# I2C.net
KiCad netlist of a schematic drawn in Altium Designer
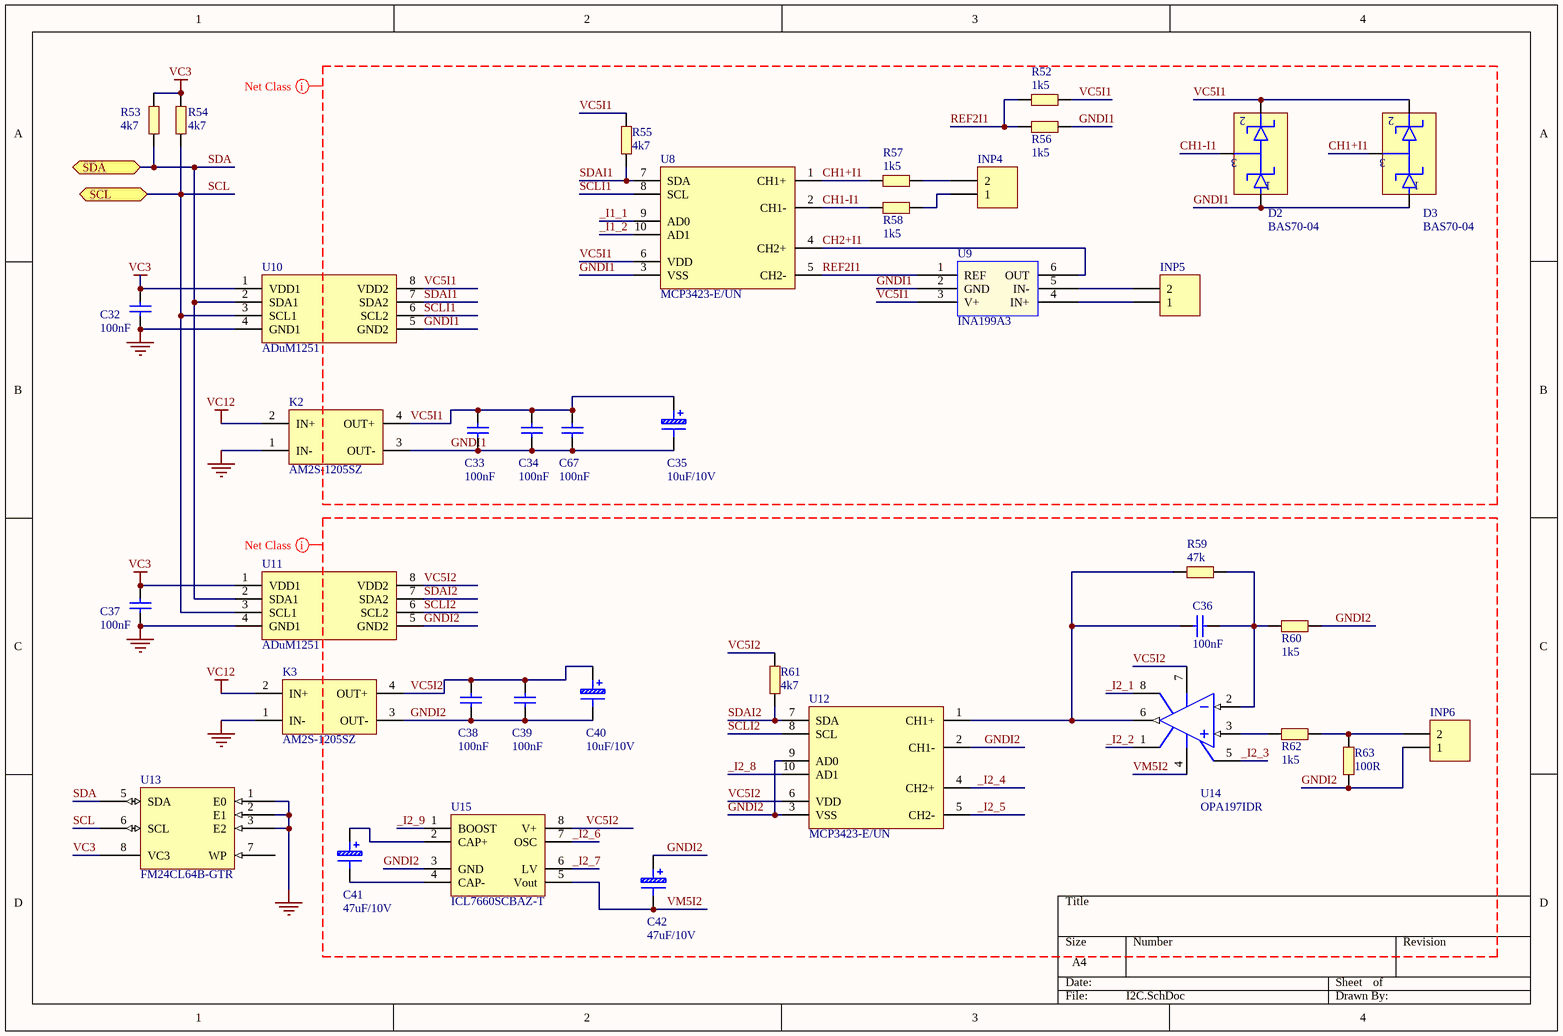
[diagram p0: I2C.SchDoc]

(export (version "E")
  (design (tool "Eeschema 10.0.6"))
  (components
    (comp (ref "C32")
      (value "100nF")
      (footprint "0603C")
      (description "Capacitor,100nF,16V,X7R,10%,0402,YAGEO")
      (libsource (lib "MCD_TOOLS") (part "Cap_100nF_X7R_10%_0402"))
    )
    (comp (ref "C33")
      (value "100nF")
      (footprint "0603C")
      (description "Capacitor,100nF,16V,X7R,10%,0402,YAGEO")
      (libsource (lib "MCD_TOOLS") (part "Cap_100nF_X7R_10%_0402"))
    )
    (comp (ref "C34")
      (value "100nF")
      (footprint "0603C")
      (description "Capacitor,100nF,16V,X7R,10%,0402,YAGEO")
      (libsource (lib "MCD_TOOLS") (part "Cap_100nF_X7R_10%_0402"))
    )
    (comp (ref "C35") (value "10uF/10V") (footprint "CAP_A") (libsource (lib "GkSchlib") (part "CapTantal")))
    (comp (ref "C36")
      (value "100nF")
      (footprint "0603C")
      (description "Capacitor,100nF,16V,X7R,10%,0402,YAGEO")
      (libsource (lib "MCD_TOOLS") (part "Cap_100nF_X7R_10%_0402"))
    )
    (comp (ref "C37")
      (value "100nF")
      (footprint "0603C")
      (description "Capacitor,100nF,16V,X7R,10%,0402,YAGEO")
      (libsource (lib "MCD_TOOLS") (part "Cap_100nF_X7R_10%_0402"))
    )
    (comp (ref "C38")
      (value "100nF")
      (footprint "0603C")
      (description "Capacitor,100nF,16V,X7R,10%,0402,YAGEO")
      (libsource (lib "MCD_TOOLS") (part "Cap_100nF_X7R_10%_0402"))
    )
    (comp (ref "C39")
      (value "100nF")
      (footprint "0603C")
      (description "Capacitor,100nF,16V,X7R,10%,0402,YAGEO")
      (libsource (lib "MCD_TOOLS") (part "Cap_100nF_X7R_10%_0402"))
    )
    (comp (ref "C40") (value "10uF/10V") (footprint "CAP_A") (libsource (lib "GkSchlib") (part "CapTantal")))
    (comp (ref "C41") (value "47uF/10V") (footprint "CAP_C") (libsource (lib "GkSchlib") (part "CapTantal")))
    (comp (ref "C42") (value "47uF/10V") (footprint "CAP_C") (libsource (lib "GkSchlib") (part "CapTantal")))
    (comp (ref "C67")
      (value "100nF")
      (footprint "0603C")
      (description "Capacitor,100nF,16V,X7R,10%,0402,YAGEO")
      (libsource (lib "MCD_TOOLS") (part "Cap_100nF_X7R_10%_0402"))
    )
    (comp (ref "D2") (value "BAS70-04") (footprint "SOT-23") (libsource (lib "*") (part "BAS70-04")))
    (comp (ref "D3") (value "BAS70-04") (footprint "SOT-23") (libsource (lib "*") (part "BAS70-04")))
    (comp (ref "INP4")
      (value "Header 2")
      (footprint "JST-XH-2Y-2.54")
      (description "Header, 2-Pin")
      (fields (field (name "PUBLISHER") "Altium Limited"))
      (libsource (lib "Miscellaneous Connectors") (part "Header 2"))
    )
    (comp (ref "INP5")
      (value "Header 2")
      (footprint "JST-XH-2Y-2.54")
      (description "Header, 2-Pin")
      (fields (field (name "PUBLISHER") "Altium Limited"))
      (libsource (lib "Miscellaneous Connectors") (part "Header 2"))
    )
    (comp (ref "INP6")
      (value "Header 2")
      (footprint "JST-XH-2Y-2.54")
      (description "Header, 2-Pin")
      (fields (field (name "PUBLISHER") "Altium Limited"))
      (libsource (lib "Miscellaneous Connectors") (part "Header 2"))
    )
    (comp (ref "K2")
      (value "AM2S-1205SZ")
      (footprint "DCDC_SIL4")
      (libsource (lib "GkSchlib") (part "DCDC_SIL"))
    )
    (comp (ref "K3")
      (value "AM2S-1205SZ")
      (footprint "DCDC_SIL4")
      (libsource (lib "GkSchlib") (part "DCDC_SIL"))
    )
    (comp (ref "R52") (value "1k5") (footprint "0603R") (libsource (lib "") (part "RES3_2")))
    (comp (ref "R53") (value "4k7") (footprint "0603R") (libsource (lib "*") (part "RES3")))
    (comp (ref "R54") (value "4k7") (footprint "0603R") (libsource (lib "*") (part "RES3")))
    (comp (ref "R55") (value "4k7") (footprint "0603R") (libsource (lib "") (part "RES3_1")))
    (comp (ref "R56") (value "1k5") (footprint "0603R") (libsource (lib "") (part "RES3_2")))
    (comp (ref "R57") (value "1k5") (footprint "0603R") (libsource (lib "") (part "RES3_2")))
    (comp (ref "R58") (value "1k5") (footprint "0603R") (libsource (lib "") (part "RES3_2")))
    (comp (ref "R59") (value "47k") (footprint "0603R") (libsource (lib "") (part "RES3_2")))
    (comp (ref "R60") (value "1k5") (footprint "0603R") (libsource (lib "") (part "RES3_2")))
    (comp (ref "R61") (value "4k7") (footprint "0603R") (libsource (lib "") (part "RES3_1")))
    (comp (ref "R62") (value "1k5") (footprint "0603R") (libsource (lib "") (part "RES3_2")))
    (comp (ref "R63") (value "100R") (footprint "0603R") (libsource (lib "") (part "RES3_1")))
    (comp (ref "U8")
      (value "MCP3423-E/UN")
      (footprint "MSOP10_1")
      (libsource (lib "GkSchlib") (part "MCP3423"))
    )
    (comp (ref "U9") (value "INA199A3") (footprint "SC70-6") (libsource (lib "GkSchlib") (part "INA199")))
    (comp (ref "U10")
      (value "ADuM1251")
      (footprint "SO8")
      (description "ADuM1251ARZ")
      (libsource (lib "GkSchlib") (part "ADuM1251"))
    )
    (comp (ref "U11")
      (value "ADuM1251")
      (footprint "SO8")
      (description "ADuM1251ARZ")
      (libsource (lib "GkSchlib") (part "ADuM1251"))
    )
    (comp (ref "U12")
      (value "MCP3423-E/UN")
      (footprint "MSOP10_1")
      (libsource (lib "GkSchlib") (part "MCP3423"))
    )
    (comp (ref "U13") (value "FM24CL64B-GTR") (footprint "SO8") (libsource (lib "*") (part "AT24C02")))
    (comp (ref "U14")
      (value "OPA197IDR")
      (footprint "SO8")
      (description "FET Operational Amplifier")
      (fields (field (name "PUBLISHER") "Altium Limited"))
      (libsource (lib "Miscellaneous Devices") (part "Op Amp"))
    )
    (comp (ref "U15")
      (value "ICL7660SCBAZ-T")
      (footprint "SO8")
      (libsource (lib "GkSchlib") (part "ICL7660"))
    )
  )
  (nets
    (net (code "1") (name "/CH1+I1") (class "Default")
      (node (ref "D3") (pin "3") (pintype "passive"))
      (node (ref "R57") (pin "1") (pintype "passive"))
      (node (ref "U8") (pin "1") (pinfunction "CH1+_1") (pintype "passive"))
    )
    (net (code "2") (name "/CH1-I1") (class "Default")
      (node (ref "D2") (pin "3") (pintype "passive"))
      (node (ref "R58") (pin "1") (pintype "passive"))
      (node (ref "U8") (pin "2") (pinfunction "CH1-_2") (pintype "passive"))
    )
    (net (code "3") (name "/CH2+I1") (class "Default")
      (node (ref "U8") (pin "4") (pinfunction "CH2+_4") (pintype "passive"))
      (node (ref "U9") (pin "6") (pinfunction "OUT_6") (pintype "passive"))
    )
    (net (code "4") (name "/GNDI1") (class "Default")
      (node (ref "C33") (pin "1") (pinfunction "1_1") (pintype "passive"))
      (node (ref "C34") (pin "1") (pinfunction "1_1") (pintype "passive"))
      (node (ref "C35") (pin "1") (pintype "passive"))
      (node (ref "C67") (pin "1") (pinfunction "1_1") (pintype "passive"))
      (node (ref "D2") (pin "1") (pintype "passive"))
      (node (ref "D3") (pin "1") (pintype "passive"))
      (node (ref "K2") (pin "3") (pinfunction "OUT-_3") (pintype "passive"))
      (node (ref "R56") (pin "2") (pintype "passive"))
      (node (ref "U10") (pin "5") (pinfunction "GND2_5") (pintype "passive"))
      (node (ref "U8") (pin "3") (pinfunction "VSS_3") (pintype "passive"))
      (node (ref "U9") (pin "2") (pinfunction "GND_2") (pintype "passive"))
    )
    (net (code "5") (name "/GNDI2") (class "Default")
      (node (ref "C38") (pin "1") (pinfunction "1_1") (pintype "passive"))
      (node (ref "C39") (pin "1") (pinfunction "1_1") (pintype "passive"))
      (node (ref "C40") (pin "1") (pintype "passive"))
      (node (ref "C42") (pin "2") (pintype "passive"))
      (node (ref "INP6") (pin "1") (pinfunction "1_1") (pintype "passive"))
      (node (ref "K3") (pin "3") (pinfunction "OUT-_3") (pintype "passive"))
      (node (ref "R60") (pin "2") (pintype "passive"))
      (node (ref "R63") (pin "1") (pintype "passive"))
      (node (ref "U11") (pin "5") (pinfunction "GND2_5") (pintype "passive"))
      (node (ref "U12") (pin "2") (pinfunction "CH1-_2") (pintype "passive"))
      (node (ref "U12") (pin "3") (pinfunction "VSS_3") (pintype "passive"))
      (node (ref "U12") (pin "9") (pinfunction "AD0_9") (pintype "passive"))
      (node (ref "U15") (pin "3") (pinfunction "GND_3") (pintype "passive"))
    )
    (net (code "6") (name "/REF2I1") (class "Default")
      (node (ref "R52") (pin "1") (pintype "passive"))
      (node (ref "R56") (pin "1") (pintype "passive"))
      (node (ref "U8") (pin "5") (pinfunction "CH2-_5") (pintype "passive"))
      (node (ref "U9") (pin "1") (pinfunction "REF_1") (pintype "passive"))
    )
    (net (code "7") (name "/SCL") (class "Default")
      (node (ref "R54") (pin "2") (pintype "passive"))
      (node (ref "U10") (pin "3") (pinfunction "SCL1_3") (pintype "passive"))
      (node (ref "U11") (pin "3") (pinfunction "SCL1_3") (pintype "passive"))
      (node (ref "U13") (pin "6") (pinfunction "SCL_6") (pintype "bidirectional"))
    )
    (net (code "8") (name "/SCLI1") (class "Default")
      (node (ref "U10") (pin "6") (pinfunction "SCL2_6") (pintype "passive"))
      (node (ref "U8") (pin "8") (pinfunction "SCL_8") (pintype "passive"))
    )
    (net (code "9") (name "/SCLI2") (class "Default")
      (node (ref "U11") (pin "6") (pinfunction "SCL2_6") (pintype "passive"))
      (node (ref "U12") (pin "8") (pinfunction "SCL_8") (pintype "passive"))
    )
    (net (code "10") (name "/SDA") (class "Default")
      (node (ref "R53") (pin "2") (pintype "passive"))
      (node (ref "U10") (pin "2") (pinfunction "SDA1_2") (pintype "passive"))
      (node (ref "U11") (pin "2") (pinfunction "SDA1_2") (pintype "passive"))
      (node (ref "U13") (pin "5") (pinfunction "SDA_5") (pintype "bidirectional"))
    )
    (net (code "11") (name "/SDAI1") (class "Default")
      (node (ref "R55") (pin "1") (pintype "passive"))
      (node (ref "U10") (pin "7") (pinfunction "SDA2_7") (pintype "passive"))
      (node (ref "U8") (pin "7") (pinfunction "SDA_7") (pintype "passive"))
    )
    (net (code "12") (name "/SDAI2") (class "Default")
      (node (ref "R61") (pin "1") (pintype "passive"))
      (node (ref "U11") (pin "7") (pinfunction "SDA2_7") (pintype "passive"))
      (node (ref "U12") (pin "7") (pinfunction "SDA_7") (pintype "passive"))
    )
    (net (code "13") (name "/VC5I1") (class "Default")
      (node (ref "C33") (pin "2") (pinfunction "2_2") (pintype "passive"))
      (node (ref "C34") (pin "2") (pinfunction "2_2") (pintype "passive"))
      (node (ref "C35") (pin "2") (pintype "passive"))
      (node (ref "C67") (pin "2") (pinfunction "2_2") (pintype "passive"))
      (node (ref "D2") (pin "2") (pintype "passive"))
      (node (ref "D3") (pin "2") (pintype "passive"))
      (node (ref "K2") (pin "4") (pinfunction "OUT+_4") (pintype "passive"))
      (node (ref "R52") (pin "2") (pintype "passive"))
      (node (ref "R55") (pin "2") (pintype "passive"))
      (node (ref "U10") (pin "8") (pinfunction "VDD2_8") (pintype "passive"))
      (node (ref "U8") (pin "6") (pinfunction "VDD_6") (pintype "passive"))
      (node (ref "U9") (pin "3") (pinfunction "V+_3") (pintype "passive"))
    )
    (net (code "14") (name "/VC5I2") (class "Default")
      (node (ref "C38") (pin "2") (pinfunction "2_2") (pintype "passive"))
      (node (ref "C39") (pin "2") (pinfunction "2_2") (pintype "passive"))
      (node (ref "C40") (pin "2") (pintype "passive"))
      (node (ref "K3") (pin "4") (pinfunction "OUT+_4") (pintype "passive"))
      (node (ref "R61") (pin "2") (pintype "passive"))
      (node (ref "U11") (pin "8") (pinfunction "VDD2_8") (pintype "passive"))
      (node (ref "U12") (pin "6") (pinfunction "VDD_6") (pintype "passive"))
      (node (ref "U14") (pin "7") (pinfunction "V+_7") (pintype "power_in"))
      (node (ref "U15") (pin "8") (pinfunction "V+_8") (pintype "passive"))
    )
    (net (code "15") (name "/VM5I2") (class "Default")
      (node (ref "C42") (pin "1") (pintype "passive"))
      (node (ref "U14") (pin "4") (pinfunction "V-_4") (pintype "power_in"))
      (node (ref "U15") (pin "5") (pinfunction "Vout_5") (pintype "passive"))
    )
    (net (code "16") (name "/_I1_1") (class "Default")
      (node (ref "U8") (pin "9") (pinfunction "AD0_9") (pintype "passive"))
    )
    (net (code "17") (name "/_I1_2") (class "Default")
      (node (ref "U8") (pin "10") (pinfunction "AD1_10") (pintype "passive"))
    )
    (net (code "18") (name "/_I2_1") (class "Default")
      (node (ref "U14") (pin "8") (pinfunction "TAB_8") (pintype "passive"))
    )
    (net (code "19") (name "/_I2_2") (class "Default")
      (node (ref "U14") (pin "1") (pinfunction "OS_NUL_1") (pintype "passive"))
    )
    (net (code "20") (name "/_I2_3") (class "Default")
      (node (ref "U14") (pin "5") (pinfunction "OS_NUL_5") (pintype "passive"))
    )
    (net (code "21") (name "/_I2_4") (class "Default")
      (node (ref "U12") (pin "4") (pinfunction "CH2+_4") (pintype "passive"))
    )
    (net (code "22") (name "/_I2_5") (class "Default")
      (node (ref "U12") (pin "5") (pinfunction "CH2-_5") (pintype "passive"))
    )
    (net (code "23") (name "/_I2_6") (class "Default")
      (node (ref "U15") (pin "7") (pinfunction "OSC_7") (pintype "passive"))
    )
    (net (code "24") (name "/_I2_7") (class "Default")
      (node (ref "U15") (pin "6") (pinfunction "LV_6") (pintype "passive"))
    )
    (net (code "25") (name "/_I2_8") (class "Default")
      (node (ref "U12") (pin "10") (pinfunction "AD1_10") (pintype "passive"))
    )
    (net (code "26") (name "/_I2_9") (class "Default")
      (node (ref "U15") (pin "1") (pinfunction "BOOST_1") (pintype "passive"))
    )
    (net (code "27") (name "GND") (class "Default")
      (node (ref "C32") (pin "1") (pinfunction "1_1") (pintype "passive"))
      (node (ref "C37") (pin "1") (pinfunction "1_1") (pintype "passive"))
      (node (ref "K2") (pin "1") (pinfunction "IN-_1") (pintype "passive"))
      (node (ref "K3") (pin "1") (pinfunction "IN-_1") (pintype "passive"))
      (node (ref "U10") (pin "4") (pinfunction "GND1_4") (pintype "passive"))
      (node (ref "U11") (pin "4") (pinfunction "GND1_4") (pintype "passive"))
      (node (ref "U13") (pin "1") (pinfunction "E0_1") (pintype "input"))
      (node (ref "U13") (pin "2") (pinfunction "E1_2") (pintype "input"))
      (node (ref "U13") (pin "3") (pinfunction "E2_3") (pintype "input"))
      (node (ref "U13") (pin "4") (pinfunction "GND_4") (pintype "power_in"))
    )
    (net (code "28") (name "Net-(INP4-Pad1)") (class "Default")
      (node (ref "INP4") (pin "1") (pinfunction "1_1") (pintype "passive"))
      (node (ref "R58") (pin "2") (pintype "passive"))
    )
    (net (code "29") (name "Net-(INP4-Pad2)") (class "Default")
      (node (ref "INP4") (pin "2") (pinfunction "2_2") (pintype "passive"))
      (node (ref "R57") (pin "2") (pintype "passive"))
    )
    (net (code "30") (name "Net-(INP6-Pad2)") (class "Default")
      (node (ref "INP6") (pin "2") (pinfunction "2_2") (pintype "passive"))
      (node (ref "R62") (pin "2") (pintype "passive"))
      (node (ref "R63") (pin "2") (pintype "passive"))
    )
    (net (code "31") (name "Net-(U9-IN+)") (class "Default")
      (node (ref "INP5") (pin "1") (pinfunction "1_1") (pintype "passive"))
      (node (ref "U9") (pin "4") (pinfunction "IN+_4") (pintype "passive"))
    )
    (net (code "32") (name "Net-(U9-IN-)") (class "Default")
      (node (ref "INP5") (pin "2") (pinfunction "2_2") (pintype "passive"))
      (node (ref "U9") (pin "5") (pinfunction "IN-_5") (pintype "passive"))
    )
    (net (code "33") (name "Net-(U12-CH1+)") (class "Default")
      (node (ref "C36") (pin "2") (pinfunction "2_2") (pintype "passive"))
      (node (ref "R59") (pin "1") (pintype "passive"))
      (node (ref "U12") (pin "1") (pinfunction "CH1+_1") (pintype "passive"))
      (node (ref "U14") (pin "6") (pinfunction "OUT_6") (pintype "output"))
    )
    (net (code "34") (name "Net-(U14-IN+)") (class "Default")
      (node (ref "R62") (pin "1") (pintype "passive"))
      (node (ref "U14") (pin "3") (pinfunction "IN+_3") (pintype "input"))
    )
    (net (code "35") (name "Net-(U14-IN-)") (class "Default")
      (node (ref "C36") (pin "1") (pinfunction "1_1") (pintype "passive"))
      (node (ref "R59") (pin "2") (pintype "passive"))
      (node (ref "R60") (pin "1") (pintype "passive"))
      (node (ref "U14") (pin "2") (pinfunction "IN-_2") (pintype "input"))
    )
    (net (code "36") (name "Net-(U15-CAP+)") (class "Default")
      (node (ref "C41") (pin "2") (pintype "passive"))
      (node (ref "U15") (pin "2") (pinfunction "CAP+_2") (pintype "passive"))
    )
    (net (code "37") (name "Net-(U15-CAP-)") (class "Default")
      (node (ref "C41") (pin "1") (pintype "passive"))
      (node (ref "U15") (pin "4") (pinfunction "CAP-_4") (pintype "passive"))
    )
    (net (code "38") (name "VC3") (class "Default")
      (node (ref "C32") (pin "2") (pinfunction "2_2") (pintype "passive"))
      (node (ref "C37") (pin "2") (pinfunction "2_2") (pintype "passive"))
      (node (ref "R53") (pin "1") (pintype "passive"))
      (node (ref "R54") (pin "1") (pintype "passive"))
      (node (ref "U10") (pin "1") (pinfunction "VDD1_1") (pintype "passive"))
      (node (ref "U11") (pin "1") (pinfunction "VDD1_1") (pintype "passive"))
      (node (ref "U13") (pin "8") (pinfunction "VC3_8") (pintype "power_in"))
    )
    (net (code "39") (name "VC12") (class "Default")
      (node (ref "K2") (pin "2") (pinfunction "IN+_2") (pintype "passive"))
      (node (ref "K3") (pin "2") (pinfunction "IN+_2") (pintype "passive"))
    )
    (net (code "40") (name "unconnected-(U13-WP-Pad7)") (class "Default")
      (node (ref "U13") (pin "7") (pinfunction "WP_7") (pintype "input"))
    )
  )
)
